# e.net
KiCad netlist of a schematic drawn in EAGLE
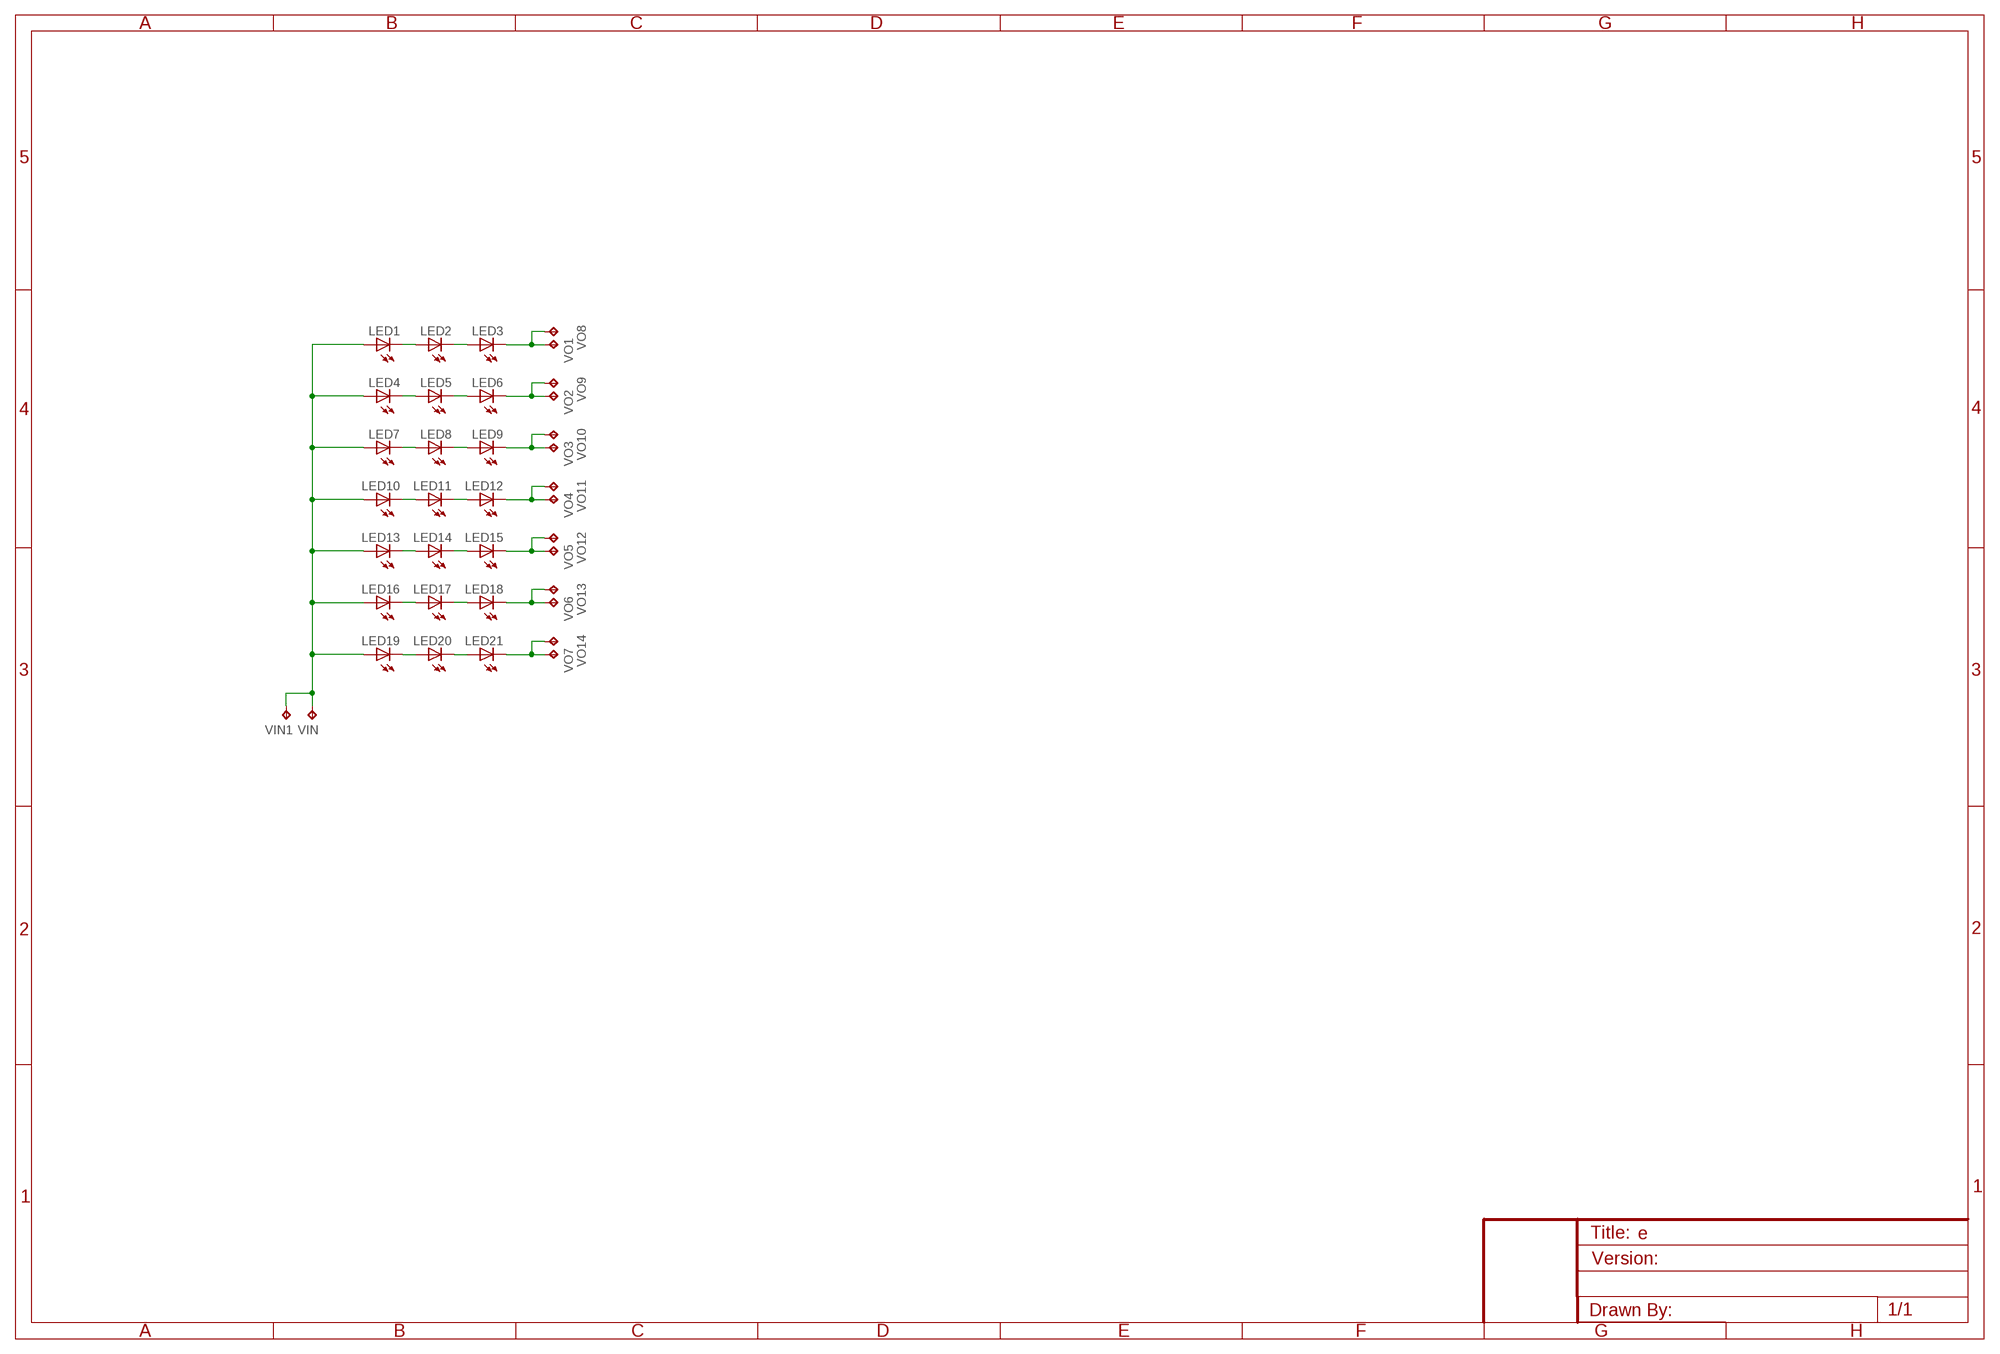
[diagram p0: schematic, sheet 1]

(export (version "E")
  (design (tool "Eeschema 10.0.6"))
  (components
    (comp (ref "LED1")
      (value "LED0805")
      (footprint "eagle-import:LED_0805")
      (libsource (lib "eagle-import") (part "LED0805"))
    )
    (comp (ref "LED2")
      (value "LED0805")
      (footprint "eagle-import:LED_0805")
      (libsource (lib "eagle-import") (part "LED0805"))
    )
    (comp (ref "LED3")
      (value "LED0805")
      (footprint "eagle-import:LED_0805")
      (libsource (lib "eagle-import") (part "LED0805"))
    )
    (comp (ref "LED4")
      (value "LED0805")
      (footprint "eagle-import:LED_0805")
      (libsource (lib "eagle-import") (part "LED0805"))
    )
    (comp (ref "LED5")
      (value "LED0805")
      (footprint "eagle-import:LED_0805")
      (libsource (lib "eagle-import") (part "LED0805"))
    )
    (comp (ref "LED6")
      (value "LED0805")
      (footprint "eagle-import:LED_0805")
      (libsource (lib "eagle-import") (part "LED0805"))
    )
    (comp (ref "LED7")
      (value "LED0805")
      (footprint "eagle-import:LED_0805")
      (libsource (lib "eagle-import") (part "LED0805"))
    )
    (comp (ref "LED8")
      (value "LED0805")
      (footprint "eagle-import:LED_0805")
      (libsource (lib "eagle-import") (part "LED0805"))
    )
    (comp (ref "LED9")
      (value "LED0805")
      (footprint "eagle-import:LED_0805")
      (libsource (lib "eagle-import") (part "LED0805"))
    )
    (comp (ref "LED10")
      (value "LED0805")
      (footprint "eagle-import:LED_0805")
      (libsource (lib "eagle-import") (part "LED0805"))
    )
    (comp (ref "LED11")
      (value "LED0805")
      (footprint "eagle-import:LED_0805")
      (libsource (lib "eagle-import") (part "LED0805"))
    )
    (comp (ref "LED12")
      (value "LED0805")
      (footprint "eagle-import:LED_0805")
      (libsource (lib "eagle-import") (part "LED0805"))
    )
    (comp (ref "LED13")
      (value "LED0805")
      (footprint "eagle-import:LED_0805")
      (libsource (lib "eagle-import") (part "LED0805"))
    )
    (comp (ref "LED14")
      (value "LED0805")
      (footprint "eagle-import:LED_0805")
      (libsource (lib "eagle-import") (part "LED0805"))
    )
    (comp (ref "LED15")
      (value "LED0805")
      (footprint "eagle-import:LED_0805")
      (libsource (lib "eagle-import") (part "LED0805"))
    )
    (comp (ref "LED16")
      (value "LED0805")
      (footprint "eagle-import:LED_0805")
      (libsource (lib "eagle-import") (part "LED0805"))
    )
    (comp (ref "LED17")
      (value "LED0805")
      (footprint "eagle-import:LED_0805")
      (libsource (lib "eagle-import") (part "LED0805"))
    )
    (comp (ref "LED18")
      (value "LED0805")
      (footprint "eagle-import:LED_0805")
      (libsource (lib "eagle-import") (part "LED0805"))
    )
    (comp (ref "LED19")
      (value "LED0805")
      (footprint "eagle-import:LED_0805")
      (libsource (lib "eagle-import") (part "LED0805"))
    )
    (comp (ref "LED20")
      (value "LED0805")
      (footprint "eagle-import:LED_0805")
      (libsource (lib "eagle-import") (part "LED0805"))
    )
    (comp (ref "LED21")
      (value "LED0805")
      (footprint "eagle-import:LED_0805")
      (libsource (lib "eagle-import") (part "LED0805"))
    )
    (comp (ref "VIN")
      (value "TEST_POINTPAD1-20")
      (footprint "eagle-import:P1-20")
      (libsource (lib "eagle-import") (part "TEST_POINTPAD1-20"))
    )
    (comp (ref "VIN1")
      (value "TEST_POINTPAD1-20")
      (footprint "eagle-import:P1-20")
      (libsource (lib "eagle-import") (part "TEST_POINTPAD1-20"))
    )
    (comp (ref "VO1")
      (value "TEST_POINTPAD1-20")
      (footprint "eagle-import:P1-20")
      (libsource (lib "eagle-import") (part "TEST_POINTPAD1-20"))
    )
    (comp (ref "VO2")
      (value "TEST_POINTPAD1-20")
      (footprint "eagle-import:P1-20")
      (libsource (lib "eagle-import") (part "TEST_POINTPAD1-20"))
    )
    (comp (ref "VO3")
      (value "TEST_POINTPAD1-20")
      (footprint "eagle-import:P1-20")
      (libsource (lib "eagle-import") (part "TEST_POINTPAD1-20"))
    )
    (comp (ref "VO4")
      (value "TEST_POINTPAD1-20")
      (footprint "eagle-import:P1-20")
      (libsource (lib "eagle-import") (part "TEST_POINTPAD1-20"))
    )
    (comp (ref "VO5")
      (value "TEST_POINTPAD1-20")
      (footprint "eagle-import:P1-20")
      (libsource (lib "eagle-import") (part "TEST_POINTPAD1-20"))
    )
    (comp (ref "VO6")
      (value "TEST_POINTPAD1-20")
      (footprint "eagle-import:P1-20")
      (libsource (lib "eagle-import") (part "TEST_POINTPAD1-20"))
    )
    (comp (ref "VO7")
      (value "TEST_POINTPAD1-20")
      (footprint "eagle-import:P1-20")
      (libsource (lib "eagle-import") (part "TEST_POINTPAD1-20"))
    )
    (comp (ref "VO8")
      (value "TEST_POINTPAD1-20")
      (footprint "eagle-import:P1-20")
      (libsource (lib "eagle-import") (part "TEST_POINTPAD1-20"))
    )
    (comp (ref "VO9")
      (value "TEST_POINTPAD1-20")
      (footprint "eagle-import:P1-20")
      (libsource (lib "eagle-import") (part "TEST_POINTPAD1-20"))
    )
    (comp (ref "VO10")
      (value "TEST_POINTPAD1-20")
      (footprint "eagle-import:P1-20")
      (libsource (lib "eagle-import") (part "TEST_POINTPAD1-20"))
    )
    (comp (ref "VO11")
      (value "TEST_POINTPAD1-20")
      (footprint "eagle-import:P1-20")
      (libsource (lib "eagle-import") (part "TEST_POINTPAD1-20"))
    )
    (comp (ref "VO12")
      (value "TEST_POINTPAD1-20")
      (footprint "eagle-import:P1-20")
      (libsource (lib "eagle-import") (part "TEST_POINTPAD1-20"))
    )
    (comp (ref "VO13")
      (value "TEST_POINTPAD1-20")
      (footprint "eagle-import:P1-20")
      (libsource (lib "eagle-import") (part "TEST_POINTPAD1-20"))
    )
    (comp (ref "VO14")
      (value "TEST_POINTPAD1-20")
      (footprint "eagle-import:P1-20")
      (libsource (lib "eagle-import") (part "TEST_POINTPAD1-20"))
    )
  )
  (nets
    (net (code "1") (name "Net-(LED1-PadA)") (class "Default")
      (node (ref "LED1") (pin "A") (pinfunction "A_A") (pintype "passive"))
      (node (ref "LED10") (pin "A") (pinfunction "A_A") (pintype "passive"))
      (node (ref "LED13") (pin "A") (pinfunction "A_A") (pintype "passive"))
      (node (ref "LED16") (pin "A") (pinfunction "A_A") (pintype "passive"))
      (node (ref "LED19") (pin "A") (pinfunction "A_A") (pintype "passive"))
      (node (ref "LED4") (pin "A") (pinfunction "A_A") (pintype "passive"))
      (node (ref "LED7") (pin "A") (pinfunction "A_A") (pintype "passive"))
      (node (ref "VIN") (pin "TP") (pinfunction "TP_TP") (pintype "input"))
      (node (ref "VIN1") (pin "TP") (pinfunction "TP_TP") (pintype "input"))
    )
    (net (code "2") (name "Net-(LED1-PadC)") (class "Default")
      (node (ref "LED1") (pin "C") (pinfunction "C_C") (pintype "passive"))
      (node (ref "LED2") (pin "A") (pinfunction "A_A") (pintype "passive"))
    )
    (net (code "3") (name "Net-(LED2-PadC)") (class "Default")
      (node (ref "LED2") (pin "C") (pinfunction "C_C") (pintype "passive"))
      (node (ref "LED3") (pin "A") (pinfunction "A_A") (pintype "passive"))
    )
    (net (code "4") (name "Net-(LED3-PadC)") (class "Default")
      (node (ref "LED3") (pin "C") (pinfunction "C_C") (pintype "passive"))
      (node (ref "VO1") (pin "TP") (pinfunction "TP_TP") (pintype "input"))
      (node (ref "VO8") (pin "TP") (pinfunction "TP_TP") (pintype "input"))
    )
    (net (code "5") (name "Net-(LED4-PadC)") (class "Default")
      (node (ref "LED4") (pin "C") (pinfunction "C_C") (pintype "passive"))
      (node (ref "LED5") (pin "A") (pinfunction "A_A") (pintype "passive"))
    )
    (net (code "6") (name "Net-(LED5-PadC)") (class "Default")
      (node (ref "LED5") (pin "C") (pinfunction "C_C") (pintype "passive"))
      (node (ref "LED6") (pin "A") (pinfunction "A_A") (pintype "passive"))
    )
    (net (code "7") (name "Net-(LED6-PadC)") (class "Default")
      (node (ref "LED6") (pin "C") (pinfunction "C_C") (pintype "passive"))
      (node (ref "VO2") (pin "TP") (pinfunction "TP_TP") (pintype "input"))
      (node (ref "VO9") (pin "TP") (pinfunction "TP_TP") (pintype "input"))
    )
    (net (code "8") (name "Net-(LED7-PadC)") (class "Default")
      (node (ref "LED7") (pin "C") (pinfunction "C_C") (pintype "passive"))
      (node (ref "LED8") (pin "A") (pinfunction "A_A") (pintype "passive"))
    )
    (net (code "9") (name "Net-(LED8-PadC)") (class "Default")
      (node (ref "LED8") (pin "C") (pinfunction "C_C") (pintype "passive"))
      (node (ref "LED9") (pin "A") (pinfunction "A_A") (pintype "passive"))
    )
    (net (code "10") (name "Net-(LED9-PadC)") (class "Default")
      (node (ref "LED9") (pin "C") (pinfunction "C_C") (pintype "passive"))
      (node (ref "VO10") (pin "TP") (pinfunction "TP_TP") (pintype "input"))
      (node (ref "VO3") (pin "TP") (pinfunction "TP_TP") (pintype "input"))
    )
    (net (code "11") (name "Net-(LED10-PadC)") (class "Default")
      (node (ref "LED10") (pin "C") (pinfunction "C_C") (pintype "passive"))
      (node (ref "LED11") (pin "A") (pinfunction "A_A") (pintype "passive"))
    )
    (net (code "12") (name "Net-(LED11-PadC)") (class "Default")
      (node (ref "LED11") (pin "C") (pinfunction "C_C") (pintype "passive"))
      (node (ref "LED12") (pin "A") (pinfunction "A_A") (pintype "passive"))
    )
    (net (code "13") (name "Net-(LED12-PadC)") (class "Default")
      (node (ref "LED12") (pin "C") (pinfunction "C_C") (pintype "passive"))
      (node (ref "VO11") (pin "TP") (pinfunction "TP_TP") (pintype "input"))
      (node (ref "VO4") (pin "TP") (pinfunction "TP_TP") (pintype "input"))
    )
    (net (code "14") (name "Net-(LED13-PadC)") (class "Default")
      (node (ref "LED13") (pin "C") (pinfunction "C_C") (pintype "passive"))
      (node (ref "LED14") (pin "A") (pinfunction "A_A") (pintype "passive"))
    )
    (net (code "15") (name "Net-(LED14-PadC)") (class "Default")
      (node (ref "LED14") (pin "C") (pinfunction "C_C") (pintype "passive"))
      (node (ref "LED15") (pin "A") (pinfunction "A_A") (pintype "passive"))
    )
    (net (code "16") (name "Net-(LED15-PadC)") (class "Default")
      (node (ref "LED15") (pin "C") (pinfunction "C_C") (pintype "passive"))
      (node (ref "VO12") (pin "TP") (pinfunction "TP_TP") (pintype "input"))
      (node (ref "VO5") (pin "TP") (pinfunction "TP_TP") (pintype "input"))
    )
    (net (code "17") (name "Net-(LED16-PadC)") (class "Default")
      (node (ref "LED16") (pin "C") (pinfunction "C_C") (pintype "passive"))
      (node (ref "LED17") (pin "A") (pinfunction "A_A") (pintype "passive"))
    )
    (net (code "18") (name "Net-(LED17-PadC)") (class "Default")
      (node (ref "LED17") (pin "C") (pinfunction "C_C") (pintype "passive"))
      (node (ref "LED18") (pin "A") (pinfunction "A_A") (pintype "passive"))
    )
    (net (code "19") (name "Net-(LED18-PadC)") (class "Default")
      (node (ref "LED18") (pin "C") (pinfunction "C_C") (pintype "passive"))
      (node (ref "VO13") (pin "TP") (pinfunction "TP_TP") (pintype "input"))
      (node (ref "VO6") (pin "TP") (pinfunction "TP_TP") (pintype "input"))
    )
    (net (code "20") (name "Net-(LED19-PadC)") (class "Default")
      (node (ref "LED19") (pin "C") (pinfunction "C_C") (pintype "passive"))
      (node (ref "LED20") (pin "A") (pinfunction "A_A") (pintype "passive"))
    )
    (net (code "21") (name "Net-(LED20-PadC)") (class "Default")
      (node (ref "LED20") (pin "C") (pinfunction "C_C") (pintype "passive"))
      (node (ref "LED21") (pin "A") (pinfunction "A_A") (pintype "passive"))
    )
    (net (code "22") (name "Net-(LED21-PadC)") (class "Default")
      (node (ref "LED21") (pin "C") (pinfunction "C_C") (pintype "passive"))
      (node (ref "VO14") (pin "TP") (pinfunction "TP_TP") (pintype "input"))
      (node (ref "VO7") (pin "TP") (pinfunction "TP_TP") (pintype "input"))
    )
  )
)
